# Boost_converter.net
KiCad netlist of a schematic drawn in EAGLE
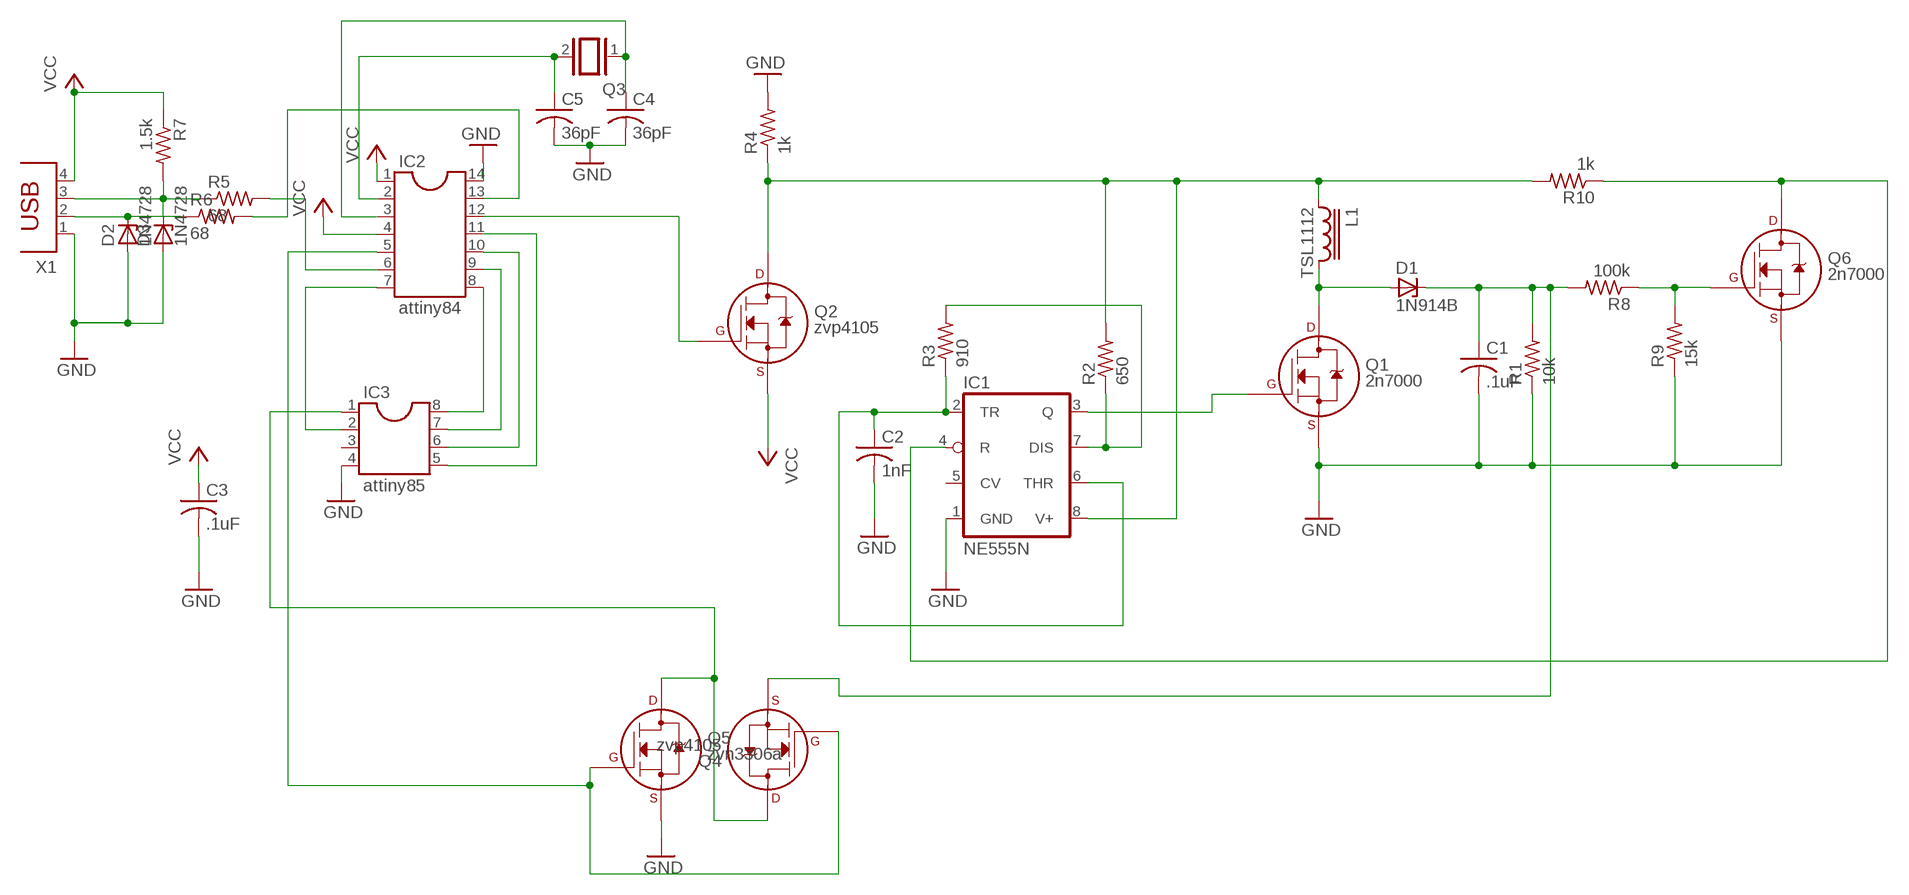
[diagram p0: schematic, sheet 1]

(export (version "E")
  (design (tool "Eeschema 10.0.6"))
  (components
    (comp (ref "C1")
      (value ".1uF")
      (footprint "eagle-import:C025-024X044")
      (libsource (lib "eagle-import") (part "C-US025-024X044"))
    )
    (comp (ref "C2")
      (value "1nF")
      (footprint "eagle-import:C025-024X044")
      (libsource (lib "eagle-import") (part "C-US025-024X044"))
    )
    (comp (ref "C3")
      (value ".1uF")
      (footprint "eagle-import:C025-024X044")
      (libsource (lib "eagle-import") (part "C-US025-024X044"))
    )
    (comp (ref "C4")
      (value "36pF")
      (footprint "eagle-import:C025-024X044")
      (libsource (lib "eagle-import") (part "C-US025-024X044"))
    )
    (comp (ref "C5")
      (value "36pF")
      (footprint "eagle-import:C025-024X044")
      (libsource (lib "eagle-import") (part "C-US025-024X044"))
    )
    (comp (ref "D1")
      (value "1N914B")
      (footprint "eagle-import:DO41Z10")
      (libsource (lib "eagle-import") (part "1N4728"))
    )
    (comp (ref "D2")
      (value "1N4728")
      (footprint "eagle-import:DO41Z10")
      (libsource (lib "eagle-import") (part "1N4728"))
    )
    (comp (ref "D3")
      (value "1N4728")
      (footprint "eagle-import:DO41Z10")
      (libsource (lib "eagle-import") (part "1N4728"))
    )
    (comp (ref "IC1")
      (value "NE555N")
      (footprint "eagle-import:DIL08-ROUND")
      (libsource (lib "eagle-import") (part "555NNE"))
    )
    (comp (ref "IC2")
      (value "attiny84")
      (footprint "eagle-import:DIL14")
      (libsource (lib "eagle-import") (part "DIL14"))
    )
    (comp (ref "IC3")
      (value "attiny85")
      (footprint "eagle-import:SOCKET-08")
      (libsource (lib "eagle-import") (part "DIL8S"))
    )
    (comp (ref "L1")
      (value "TSL1112")
      (footprint "eagle-import:TSL1112")
      (libsource (lib "eagle-import") (part "TSL1112"))
    )
    (comp (ref "Q1")
      (value "2n7000")
      (footprint "eagle-import:TO-92")
      (libsource (lib "eagle-import") (part "2N700_TO920"))
    )
    (comp (ref "Q2")
      (value "zvp4105")
      (footprint "eagle-import:TO-92")
      (libsource (lib "eagle-import") (part "2N700_TO920"))
    )
    (comp (ref "Q3")
      (value "XTAL/S")
      (footprint "eagle-import:QS")
      (libsource (lib "eagle-import") (part "XTAL/S"))
    )
    (comp (ref "Q4")
      (value "zvp4105")
      (footprint "eagle-import:TO-92")
      (libsource (lib "eagle-import") (part "2N700_TO920"))
    )
    (comp (ref "Q5")
      (value "zvn3306a")
      (footprint "eagle-import:TO-92")
      (libsource (lib "eagle-import") (part "2N700_TO920"))
    )
    (comp (ref "Q6")
      (value "2n7000")
      (footprint "eagle-import:TO-92")
      (libsource (lib "eagle-import") (part "2N700_TO920"))
    )
    (comp (ref "R1")
      (value "10k")
      (footprint "eagle-import:0204_7")
      (libsource (lib "eagle-import") (part "R-US_0204/7"))
    )
    (comp (ref "R2")
      (value "650")
      (footprint "eagle-import:0204_7")
      (libsource (lib "eagle-import") (part "R-US_0204/7"))
    )
    (comp (ref "R3")
      (value "910")
      (footprint "eagle-import:0204_7")
      (libsource (lib "eagle-import") (part "R-US_0204/7"))
    )
    (comp (ref "R4")
      (value "1k")
      (footprint "eagle-import:0204_7")
      (libsource (lib "eagle-import") (part "R-US_0204/7"))
    )
    (comp (ref "R5")
      (value "68")
      (footprint "eagle-import:0204_7")
      (libsource (lib "eagle-import") (part "R-US_0204/7"))
    )
    (comp (ref "R6")
      (value "68")
      (footprint "eagle-import:0204_7")
      (libsource (lib "eagle-import") (part "R-US_0204/7"))
    )
    (comp (ref "R7")
      (value "1.5k")
      (footprint "eagle-import:0204_7")
      (libsource (lib "eagle-import") (part "R-US_0204/7"))
    )
    (comp (ref "R8")
      (value "100k")
      (footprint "eagle-import:0204_7")
      (libsource (lib "eagle-import") (part "R-US_0204/7"))
    )
    (comp (ref "R9")
      (value "15k")
      (footprint "eagle-import:0204_7")
      (libsource (lib "eagle-import") (part "R-US_0204/7"))
    )
    (comp (ref "R10")
      (value "1k")
      (footprint "eagle-import:0204_7")
      (libsource (lib "eagle-import") (part "R-US_0204/7"))
    )
    (comp (ref "X1")
      (value "PN87520")
      (footprint "eagle-import:PN87520")
      (libsource (lib "eagle-import") (part "PN87520"))
    )
  )
  (nets
    (net (code "1") (name "GND") (class "Default")
      (node (ref "C1") (pin "2") (pinfunction "2_2") (pintype "passive"))
      (node (ref "C2") (pin "2") (pinfunction "2_2") (pintype "passive"))
      (node (ref "C3") (pin "2") (pinfunction "2_2") (pintype "passive"))
      (node (ref "C4") (pin "2") (pinfunction "2_2") (pintype "passive"))
      (node (ref "C5") (pin "2") (pinfunction "2_2") (pintype "passive"))
      (node (ref "D2") (pin "A") (pinfunction "A_A") (pintype "passive"))
      (node (ref "D3") (pin "A") (pinfunction "A_A") (pintype "passive"))
      (node (ref "IC1") (pin "1") (pinfunction "GND_1") (pintype "power_in"))
      (node (ref "IC2") (pin "14") (pinfunction "14_14") (pintype "passive"))
      (node (ref "IC3") (pin "4") (pinfunction "4_4") (pintype "passive"))
      (node (ref "Q1") (pin "1") (pinfunction "S_1") (pintype "bidirectional"))
      (node (ref "Q5") (pin "1") (pinfunction "S_1") (pintype "bidirectional"))
      (node (ref "Q6") (pin "1") (pinfunction "S_1") (pintype "bidirectional"))
      (node (ref "R1") (pin "1") (pinfunction "1_1") (pintype "passive"))
      (node (ref "R4") (pin "2") (pinfunction "2_2") (pintype "passive"))
      (node (ref "R9") (pin "1") (pinfunction "1_1") (pintype "passive"))
      (node (ref "X1") (pin "1") (pinfunction "1_1") (pintype "passive"))
    )
    (net (code "2") (name "Net-(C4-Pad1)") (class "Default")
      (node (ref "C4") (pin "1") (pinfunction "1_1") (pintype "passive"))
      (node (ref "IC2") (pin "3") (pinfunction "3_3") (pintype "passive"))
      (node (ref "Q3") (pin "1") (pinfunction "1_1") (pintype "passive"))
    )
    (net (code "3") (name "Net-(C5-Pad1)") (class "Default")
      (node (ref "C5") (pin "1") (pinfunction "1_1") (pintype "passive"))
      (node (ref "IC2") (pin "2") (pinfunction "2_2") (pintype "passive"))
      (node (ref "Q3") (pin "2") (pinfunction "2_2") (pintype "passive"))
    )
    (net (code "4") (name "Net-(D2-PadC)") (class "Default")
      (node (ref "D2") (pin "C") (pinfunction "C_C") (pintype "passive"))
      (node (ref "R6") (pin "1") (pinfunction "1_1") (pintype "passive"))
      (node (ref "X1") (pin "2") (pinfunction "2_2") (pintype "passive"))
    )
    (net (code "5") (name "Net-(D3-PadC)") (class "Default")
      (node (ref "D3") (pin "C") (pinfunction "C_C") (pintype "passive"))
      (node (ref "R5") (pin "1") (pinfunction "1_1") (pintype "passive"))
      (node (ref "R7") (pin "2") (pinfunction "2_2") (pintype "passive"))
      (node (ref "X1") (pin "3") (pinfunction "3_3") (pintype "passive"))
    )
    (net (code "6") (name "Net-(IC1-DIS)") (class "Default")
      (node (ref "IC1") (pin "7") (pinfunction "DIS_7") (pintype "input"))
      (node (ref "R2") (pin "1") (pinfunction "1_1") (pintype "passive"))
      (node (ref "R3") (pin "2") (pinfunction "2_2") (pintype "passive"))
    )
    (net (code "7") (name "Net-(IC1-Q)") (class "Default")
      (node (ref "IC1") (pin "3") (pinfunction "Q_3") (pintype "output"))
      (node (ref "Q1") (pin "2") (pinfunction "G_2") (pintype "tri_state"))
    )
    (net (code "8") (name "Net-(IC1-R)") (class "Default")
      (node (ref "IC1") (pin "4") (pinfunction "R_4") (pintype "input"))
      (node (ref "Q6") (pin "3") (pinfunction "D_3") (pintype "bidirectional"))
      (node (ref "R10") (pin "1") (pinfunction "1_1") (pintype "passive"))
    )
    (net (code "9") (name "Net-(IC1-THR)") (class "Default")
      (node (ref "C2") (pin "1") (pinfunction "1_1") (pintype "passive"))
      (node (ref "IC1") (pin "2") (pinfunction "TR_2") (pintype "input"))
      (node (ref "IC1") (pin "6") (pinfunction "THR_6") (pintype "input"))
      (node (ref "R3") (pin "1") (pinfunction "1_1") (pintype "passive"))
    )
    (net (code "10") (name "Net-(IC1-V+)") (class "Default")
      (node (ref "IC1") (pin "8") (pinfunction "V+_8") (pintype "power_in"))
      (node (ref "L1") (pin "1") (pinfunction "1_1") (pintype "passive"))
      (node (ref "Q2") (pin "3") (pinfunction "D_3") (pintype "bidirectional"))
      (node (ref "R10") (pin "2") (pinfunction "2_2") (pintype "passive"))
      (node (ref "R2") (pin "2") (pinfunction "2_2") (pintype "passive"))
      (node (ref "R4") (pin "1") (pinfunction "1_1") (pintype "passive"))
    )
    (net (code "11") (name "Net-(IC2-Pad6)") (class "Default")
      (node (ref "IC2") (pin "6") (pinfunction "6_6") (pintype "passive"))
      (node (ref "R5") (pin "2") (pinfunction "2_2") (pintype "passive"))
    )
    (net (code "12") (name "Net-(IC2-Pad7)") (class "Default")
      (node (ref "IC2") (pin "7") (pinfunction "7_7") (pintype "passive"))
      (node (ref "IC3") (pin "2") (pinfunction "2_2") (pintype "passive"))
    )
    (net (code "13") (name "Net-(IC2-Pad8)") (class "Default")
      (node (ref "IC2") (pin "8") (pinfunction "8_8") (pintype "passive"))
      (node (ref "IC3") (pin "8") (pinfunction "8_8") (pintype "passive"))
    )
    (net (code "14") (name "Net-(IC2-Pad9)") (class "Default")
      (node (ref "IC2") (pin "9") (pinfunction "9_9") (pintype "passive"))
      (node (ref "IC3") (pin "7") (pinfunction "7_7") (pintype "passive"))
    )
    (net (code "15") (name "Net-(IC2-Pad10)") (class "Default")
      (node (ref "IC2") (pin "10") (pinfunction "10_10") (pintype "passive"))
      (node (ref "IC3") (pin "6") (pinfunction "6_6") (pintype "passive"))
    )
    (net (code "16") (name "Net-(IC2-Pad11)") (class "Default")
      (node (ref "IC2") (pin "11") (pinfunction "11_11") (pintype "passive"))
      (node (ref "IC3") (pin "5") (pinfunction "5_5") (pintype "passive"))
    )
    (net (code "17") (name "Net-(IC2-Pad13)") (class "Default")
      (node (ref "IC2") (pin "13") (pinfunction "13_13") (pintype "passive"))
      (node (ref "R6") (pin "2") (pinfunction "2_2") (pintype "passive"))
    )
    (net (code "18") (name "Net-(Q1-D)") (class "Default")
      (node (ref "D1") (pin "A") (pinfunction "A_A") (pintype "passive"))
      (node (ref "L1") (pin "2") (pinfunction "2_2") (pintype "passive"))
      (node (ref "Q1") (pin "3") (pinfunction "D_3") (pintype "bidirectional"))
    )
    (net (code "19") (name "Net-(Q2-G)") (class "Default")
      (node (ref "IC2") (pin "12") (pinfunction "12_12") (pintype "passive"))
      (node (ref "Q2") (pin "2") (pinfunction "G_2") (pintype "tri_state"))
    )
    (net (code "20") (name "Net-(Q4-D)") (class "Default")
      (node (ref "IC3") (pin "1") (pinfunction "1_1") (pintype "passive"))
      (node (ref "Q4") (pin "3") (pinfunction "D_3") (pintype "bidirectional"))
      (node (ref "Q5") (pin "3") (pinfunction "D_3") (pintype "bidirectional"))
    )
    (net (code "21") (name "Net-(Q4-G)") (class "Default")
      (node (ref "IC2") (pin "5") (pinfunction "5_5") (pintype "passive"))
      (node (ref "Q4") (pin "2") (pinfunction "G_2") (pintype "tri_state"))
      (node (ref "Q5") (pin "2") (pinfunction "G_2") (pintype "tri_state"))
    )
    (net (code "22") (name "Net-(Q4-S)") (class "Default")
      (node (ref "C1") (pin "1") (pinfunction "1_1") (pintype "passive"))
      (node (ref "D1") (pin "C") (pinfunction "C_C") (pintype "passive"))
      (node (ref "Q4") (pin "1") (pinfunction "S_1") (pintype "bidirectional"))
      (node (ref "R1") (pin "2") (pinfunction "2_2") (pintype "passive"))
      (node (ref "R8") (pin "2") (pinfunction "2_2") (pintype "passive"))
    )
    (net (code "23") (name "Net-(Q6-G)") (class "Default")
      (node (ref "Q6") (pin "2") (pinfunction "G_2") (pintype "tri_state"))
      (node (ref "R8") (pin "1") (pinfunction "1_1") (pintype "passive"))
      (node (ref "R9") (pin "2") (pinfunction "2_2") (pintype "passive"))
    )
    (net (code "24") (name "VCC") (class "Default")
      (node (ref "C3") (pin "1") (pinfunction "1_1") (pintype "passive"))
      (node (ref "IC2") (pin "1") (pinfunction "1_1") (pintype "passive"))
      (node (ref "IC2") (pin "4") (pinfunction "4_4") (pintype "passive"))
      (node (ref "Q2") (pin "1") (pinfunction "S_1") (pintype "bidirectional"))
      (node (ref "R7") (pin "1") (pinfunction "1_1") (pintype "passive"))
      (node (ref "X1") (pin "4") (pinfunction "4_4") (pintype "passive"))
    )
    (net (code "25") (name "unconnected-(IC1-CV-Pad5)") (class "Default")
      (node (ref "IC1") (pin "5") (pinfunction "CV_5") (pintype "input"))
    )
    (net (code "26") (name "unconnected-(IC3-Pad3)") (class "Default")
      (node (ref "IC3") (pin "3") (pinfunction "3_3") (pintype "passive"))
    )
  )
)
